# Single_TH.net
KiCad netlist of a schematic drawn in EAGLE
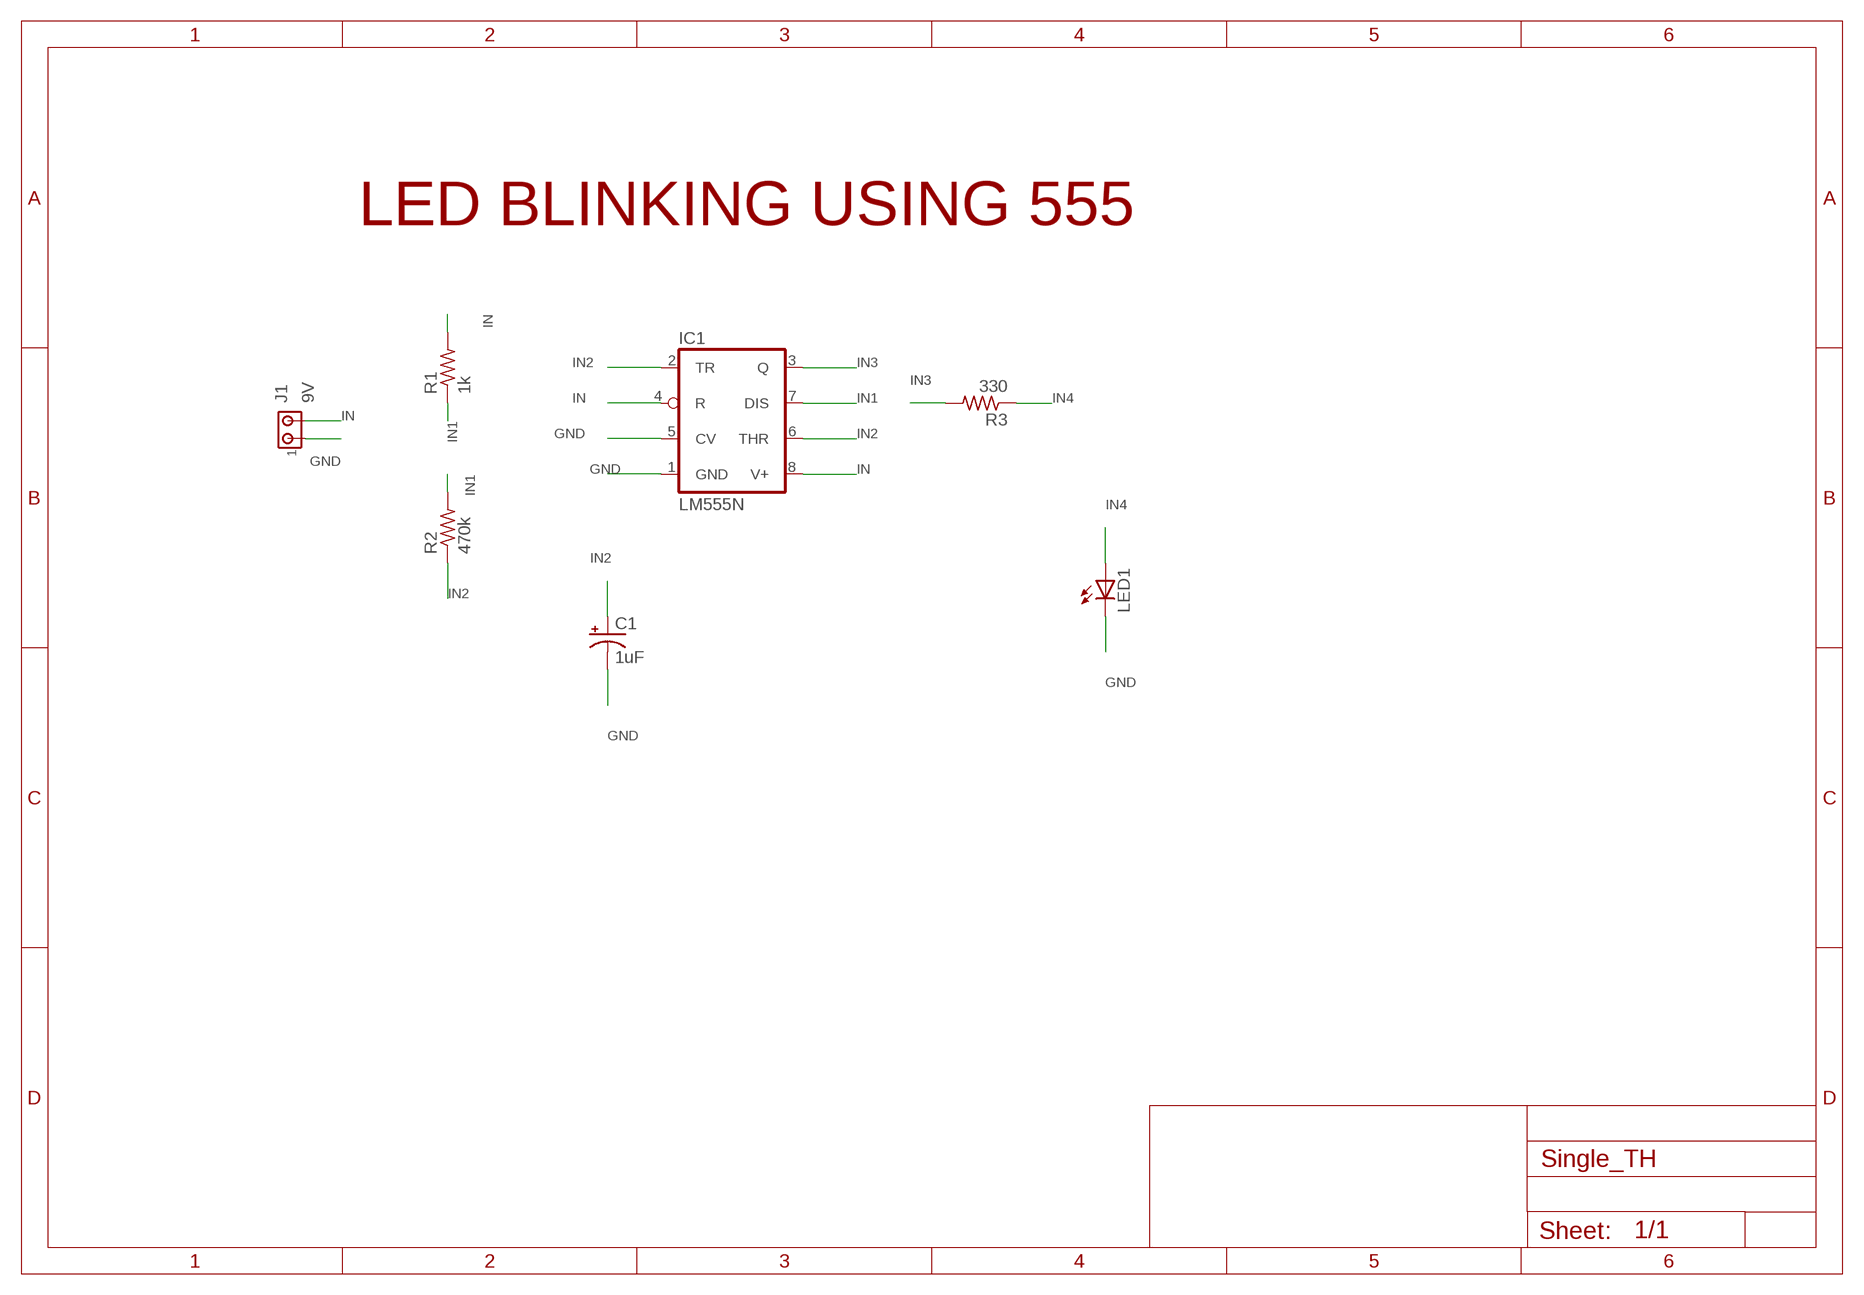
[diagram p0: schematic, sheet 1]

(export (version "E")
  (design (tool "Eeschema 10.0.6"))
  (components
    (comp (ref "C1")
      (value "1uF")
      (footprint "eagle-import:E2,5-7")
      (libsource (lib "eagle-import") (part "CPOL-USE2.5-7"))
    )
    (comp (ref "IC1")
      (value "LM555N")
      (footprint "eagle-import:DIL08")
      (libsource (lib "eagle-import") (part "555NLM"))
    )
    (comp (ref "J1")
      (value "9V")
      (footprint "eagle-import:1X2MTA")
      (libsource (lib "eagle-import") (part "MTA02-156"))
    )
    (comp (ref "LED1")
      (value "LED5MM")
      (footprint "eagle-import:LED5MM")
      (libsource (lib "eagle-import") (part "LED5MM"))
    )
    (comp (ref "R1")
      (value "1k")
      (footprint "eagle-import:0204_5")
      (libsource (lib "eagle-import") (part "R-US_0204/5"))
    )
    (comp (ref "R2")
      (value "470k")
      (footprint "eagle-import:0204_5")
      (libsource (lib "eagle-import") (part "R-US_0204/5"))
    )
    (comp (ref "R3")
      (value "330")
      (footprint "eagle-import:0204_5")
      (libsource (lib "eagle-import") (part "R-US_0204/5"))
    )
  )
  (nets
    (net (code "1") (name "/GND") (class "Default")
      (node (ref "C1") (pin "-") (pinfunction "-_-") (pintype "passive"))
      (node (ref "IC1") (pin "1") (pinfunction "GND_1") (pintype "power_in"))
      (node (ref "IC1") (pin "5") (pinfunction "CV_5") (pintype "input"))
      (node (ref "J1") (pin "1") (pinfunction "1_1") (pintype "passive"))
      (node (ref "LED1") (pin "K") (pinfunction "C_K") (pintype "passive"))
    )
    (net (code "2") (name "/IN") (class "Default")
      (node (ref "IC1") (pin "4") (pinfunction "R_4") (pintype "input"))
      (node (ref "IC1") (pin "8") (pinfunction "V+_8") (pintype "power_in"))
      (node (ref "J1") (pin "2") (pinfunction "2_2") (pintype "passive"))
      (node (ref "R1") (pin "2") (pinfunction "2_2") (pintype "passive"))
    )
    (net (code "3") (name "/IN1") (class "Default")
      (node (ref "IC1") (pin "7") (pinfunction "DIS_7") (pintype "input"))
      (node (ref "R1") (pin "1") (pinfunction "1_1") (pintype "passive"))
      (node (ref "R2") (pin "2") (pinfunction "2_2") (pintype "passive"))
    )
    (net (code "4") (name "/IN2") (class "Default")
      (node (ref "C1") (pin "+") (pinfunction "+_+") (pintype "passive"))
      (node (ref "IC1") (pin "2") (pinfunction "TR_2") (pintype "input"))
      (node (ref "IC1") (pin "6") (pinfunction "THR_6") (pintype "input"))
      (node (ref "R2") (pin "1") (pinfunction "1_1") (pintype "passive"))
    )
    (net (code "5") (name "/IN3") (class "Default")
      (node (ref "IC1") (pin "3") (pinfunction "Q_3") (pintype "output"))
      (node (ref "R3") (pin "2") (pinfunction "2_2") (pintype "passive"))
    )
    (net (code "6") (name "/IN4") (class "Default")
      (node (ref "LED1") (pin "A") (pinfunction "A_A") (pintype "passive"))
      (node (ref "R3") (pin "1") (pinfunction "1_1") (pintype "passive"))
    )
  )
)
